# TCA9548A.net
KiCad netlist of a schematic drawn in Altium Designer
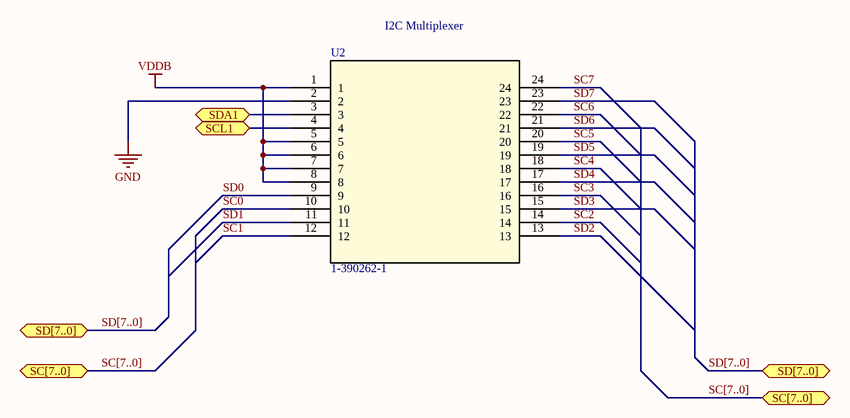
[diagram p0: TCA9548A.SchDoc]

(export (version "E")
  (design (tool "Eeschema 10.0.6"))
  (components
    (comp (ref "U2")
      (value "1-390262-1")
      (footprint "1-390262-1:1-390262-1_TYC")
      (description "No Description Available")
      (fields (field (name "COPYRIGHT") "Copyright (C) 2022 Ultra Librarian. All rights reserved."))
      (libsource (lib "1-390262-1") (part "1-390262-1"))
    )
  )
  (nets
    (net (code "1") (name "/SC0") (class "Default")
      (node (ref "U2") (pin "10") (pinfunction "10_10") (pintype "passive"))
    )
    (net (code "2") (name "/SC1") (class "Default")
      (node (ref "U2") (pin "12") (pinfunction "12_12") (pintype "passive"))
    )
    (net (code "3") (name "/SC2") (class "Default")
      (node (ref "U2") (pin "14") (pinfunction "14_14") (pintype "passive"))
    )
    (net (code "4") (name "/SC3") (class "Default")
      (node (ref "U2") (pin "16") (pinfunction "16_16") (pintype "passive"))
    )
    (net (code "5") (name "/SC4") (class "Default")
      (node (ref "U2") (pin "18") (pinfunction "18_18") (pintype "passive"))
    )
    (net (code "6") (name "/SC5") (class "Default")
      (node (ref "U2") (pin "20") (pinfunction "20_20") (pintype "passive"))
    )
    (net (code "7") (name "/SC6") (class "Default")
      (node (ref "U2") (pin "22") (pinfunction "22_22") (pintype "passive"))
    )
    (net (code "8") (name "/SC7") (class "Default")
      (node (ref "U2") (pin "24") (pinfunction "24_24") (pintype "passive"))
    )
    (net (code "9") (name "/SCL1") (class "Default")
      (node (ref "U2") (pin "4") (pinfunction "4_4") (pintype "passive"))
    )
    (net (code "11") (name "/SD0") (class "Default")
      (node (ref "U2") (pin "9") (pinfunction "9_9") (pintype "passive"))
    )
    (net (code "12") (name "/SD1") (class "Default")
      (node (ref "U2") (pin "11") (pinfunction "11_11") (pintype "passive"))
    )
    (net (code "13") (name "/SD2") (class "Default")
      (node (ref "U2") (pin "13") (pinfunction "13_13") (pintype "passive"))
    )
    (net (code "14") (name "/SD3") (class "Default")
      (node (ref "U2") (pin "15") (pinfunction "15_15") (pintype "passive"))
    )
    (net (code "15") (name "/SD4") (class "Default")
      (node (ref "U2") (pin "17") (pinfunction "17_17") (pintype "passive"))
    )
    (net (code "16") (name "/SD5") (class "Default")
      (node (ref "U2") (pin "19") (pinfunction "19_19") (pintype "passive"))
    )
    (net (code "17") (name "/SD6") (class "Default")
      (node (ref "U2") (pin "21") (pinfunction "21_21") (pintype "passive"))
    )
    (net (code "18") (name "/SD7") (class "Default")
      (node (ref "U2") (pin "23") (pinfunction "23_23") (pintype "passive"))
    )
    (net (code "19") (name "/SDA1") (class "Default")
      (node (ref "U2") (pin "3") (pinfunction "3_3") (pintype "passive"))
    )
    (net (code "21") (name "GND") (class "Default")
      (node (ref "U2") (pin "2") (pinfunction "2_2") (pintype "passive"))
    )
    (net (code "22") (name "VDDB") (class "Default")
      (node (ref "U2") (pin "1") (pinfunction "1_1") (pintype "passive"))
      (node (ref "U2") (pin "5") (pinfunction "5_5") (pintype "passive"))
      (node (ref "U2") (pin "6") (pinfunction "6_6") (pintype "passive"))
      (node (ref "U2") (pin "7") (pinfunction "7_7") (pintype "passive"))
      (node (ref "U2") (pin "8") (pinfunction "8_8") (pintype "passive"))
    )
  )
)
